# oa_sevenfortyfun.net
KiCad netlist of a schematic drawn in EAGLE
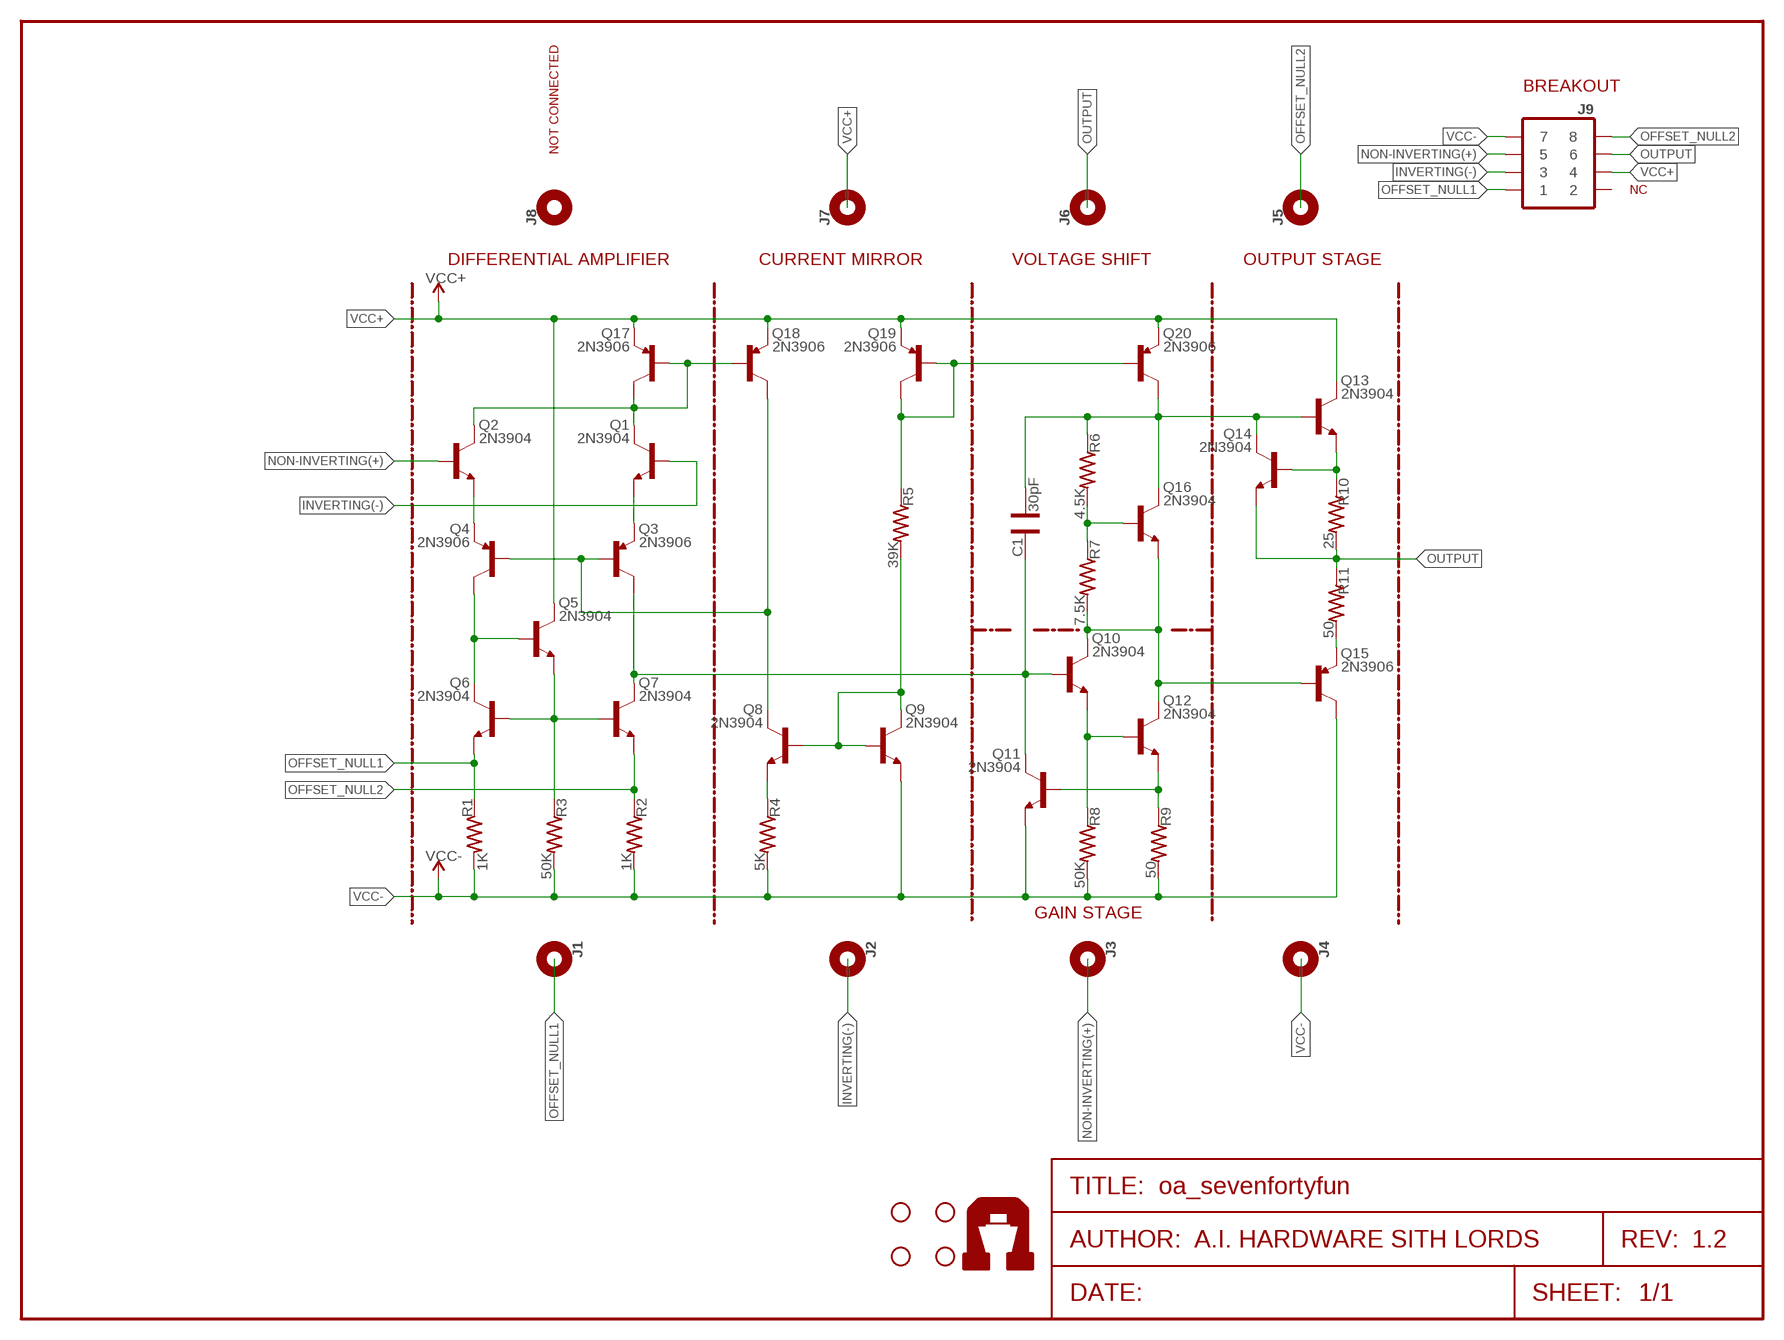
[diagram p0: schematic, sheet 1]

(export (version "E")
  (design (tool "Eeschema 10.0.6"))
  (components
    (comp (ref "C1")
      (value "30pF")
      (footprint "eagle-import:CAP-025X050")
      (libsource (lib "eagle-import") (part "CAP025X050"))
    )
    (comp (ref "J1")
      (value "1X01-TERM")
      (footprint "eagle-import:1X01-TERM")
      (libsource (lib "eagle-import") (part "1X01-TERM"))
    )
    (comp (ref "J2")
      (value "1X01-TERM")
      (footprint "eagle-import:1X01-TERM")
      (libsource (lib "eagle-import") (part "1X01-TERM"))
    )
    (comp (ref "J3")
      (value "1X01-TERM")
      (footprint "eagle-import:1X01-TERM")
      (libsource (lib "eagle-import") (part "1X01-TERM"))
    )
    (comp (ref "J4")
      (value "1X01-TERM")
      (footprint "eagle-import:1X01-TERM")
      (libsource (lib "eagle-import") (part "1X01-TERM"))
    )
    (comp (ref "J5")
      (value "1X01-TERM")
      (footprint "eagle-import:1X01-TERM")
      (libsource (lib "eagle-import") (part "1X01-TERM"))
    )
    (comp (ref "J6")
      (value "1X01-TERM")
      (footprint "eagle-import:1X01-TERM")
      (libsource (lib "eagle-import") (part "1X01-TERM"))
    )
    (comp (ref "J7")
      (value "1X01-TERM")
      (footprint "eagle-import:1X01-TERM")
      (libsource (lib "eagle-import") (part "1X01-TERM"))
    )
    (comp (ref "J8")
      (value "1X01-TERM")
      (footprint "eagle-import:1X01-TERM")
      (libsource (lib "eagle-import") (part "1X01-TERM"))
    )
    (comp (ref "J9")
      (value "2X04SHR")
      (footprint "eagle-import:2X04-SHR")
      (libsource (lib "eagle-import") (part "2X04SHR"))
    )
    (comp (ref "Q1")
      (value "2N3904")
      (footprint "eagle-import:TO-92-NPN")
      (libsource (lib "eagle-import") (part "BJT-NPN"))
    )
    (comp (ref "Q2")
      (value "2N3904")
      (footprint "eagle-import:TO-92-NPN")
      (libsource (lib "eagle-import") (part "BJT-NPN"))
    )
    (comp (ref "Q3")
      (value "2N3906")
      (footprint "eagle-import:TO-92-PNP")
      (libsource (lib "eagle-import") (part "BJT-PNP"))
    )
    (comp (ref "Q4")
      (value "2N3906")
      (footprint "eagle-import:TO-92-PNP")
      (libsource (lib "eagle-import") (part "BJT-PNP"))
    )
    (comp (ref "Q5")
      (value "2N3904")
      (footprint "eagle-import:TO-92-NPN")
      (libsource (lib "eagle-import") (part "BJT-NPN"))
    )
    (comp (ref "Q6")
      (value "2N3904")
      (footprint "eagle-import:TO-92-NPN")
      (libsource (lib "eagle-import") (part "BJT-NPN"))
    )
    (comp (ref "Q7")
      (value "2N3904")
      (footprint "eagle-import:TO-92-NPN")
      (libsource (lib "eagle-import") (part "BJT-NPN"))
    )
    (comp (ref "Q8")
      (value "2N3904")
      (footprint "eagle-import:TO-92-NPN")
      (libsource (lib "eagle-import") (part "BJT-NPN"))
    )
    (comp (ref "Q9")
      (value "2N3904")
      (footprint "eagle-import:TO-92-NPN")
      (libsource (lib "eagle-import") (part "BJT-NPN"))
    )
    (comp (ref "Q10")
      (value "2N3904")
      (footprint "eagle-import:TO-92-NPN")
      (libsource (lib "eagle-import") (part "BJT-NPN"))
    )
    (comp (ref "Q11")
      (value "2N3904")
      (footprint "eagle-import:TO-92-NPN")
      (libsource (lib "eagle-import") (part "BJT-NPN"))
    )
    (comp (ref "Q12")
      (value "2N3904")
      (footprint "eagle-import:TO-92-NPN")
      (libsource (lib "eagle-import") (part "BJT-NPN"))
    )
    (comp (ref "Q13")
      (value "2N3904")
      (footprint "eagle-import:TO-92-NPN")
      (libsource (lib "eagle-import") (part "BJT-NPN"))
    )
    (comp (ref "Q14")
      (value "2N3904")
      (footprint "eagle-import:TO-92-NPN")
      (libsource (lib "eagle-import") (part "BJT-NPN"))
    )
    (comp (ref "Q15")
      (value "2N3906")
      (footprint "eagle-import:TO-92-PNP")
      (libsource (lib "eagle-import") (part "BJT-PNP"))
    )
    (comp (ref "Q16")
      (value "2N3904")
      (footprint "eagle-import:TO-92-NPN")
      (libsource (lib "eagle-import") (part "BJT-NPN"))
    )
    (comp (ref "Q17")
      (value "2N3906")
      (footprint "eagle-import:TO-92-PNP")
      (libsource (lib "eagle-import") (part "BJT-PNP"))
    )
    (comp (ref "Q18")
      (value "2N3906")
      (footprint "eagle-import:TO-92-PNP")
      (libsource (lib "eagle-import") (part "BJT-PNP"))
    )
    (comp (ref "Q19")
      (value "2N3906")
      (footprint "eagle-import:TO-92-PNP")
      (libsource (lib "eagle-import") (part "BJT-PNP"))
    )
    (comp (ref "Q20")
      (value "2N3906")
      (footprint "eagle-import:TO-92-PNP")
      (libsource (lib "eagle-import") (part "BJT-PNP"))
    )
    (comp (ref "R1")
      (value "1K")
      (footprint "eagle-import:RES-AXIAL-0.4")
      (libsource (lib "eagle-import") (part "RESAXIAL-0.4"))
    )
    (comp (ref "R2")
      (value "1K")
      (footprint "eagle-import:RES-AXIAL-0.4")
      (libsource (lib "eagle-import") (part "RESAXIAL-0.4"))
    )
    (comp (ref "R3")
      (value "50K")
      (footprint "eagle-import:RES-AXIAL-0.4")
      (libsource (lib "eagle-import") (part "RESAXIAL-0.4"))
    )
    (comp (ref "R4")
      (value "5K")
      (footprint "eagle-import:RES-AXIAL-0.4")
      (libsource (lib "eagle-import") (part "RESAXIAL-0.4"))
    )
    (comp (ref "R5")
      (value "39K")
      (footprint "eagle-import:RES-AXIAL-0.4")
      (libsource (lib "eagle-import") (part "RESAXIAL-0.4"))
    )
    (comp (ref "R6")
      (value "4.5K")
      (footprint "eagle-import:RES-AXIAL-0.4")
      (libsource (lib "eagle-import") (part "RESAXIAL-0.4"))
    )
    (comp (ref "R7")
      (value "7.5K")
      (footprint "eagle-import:RES-AXIAL-0.4")
      (libsource (lib "eagle-import") (part "RESAXIAL-0.4"))
    )
    (comp (ref "R8")
      (value "50K")
      (footprint "eagle-import:RES-AXIAL-0.4")
      (libsource (lib "eagle-import") (part "RESAXIAL-0.4"))
    )
    (comp (ref "R9")
      (value "50")
      (footprint "eagle-import:RES-AXIAL-0.4")
      (libsource (lib "eagle-import") (part "RESAXIAL-0.4"))
    )
    (comp (ref "R10")
      (value "25")
      (footprint "eagle-import:RES-AXIAL-0.4")
      (libsource (lib "eagle-import") (part "RESAXIAL-0.4"))
    )
    (comp (ref "R11")
      (value "50")
      (footprint "eagle-import:RES-AXIAL-0.4")
      (libsource (lib "eagle-import") (part "RESAXIAL-0.4"))
    )
    (comp (ref "STANDOFF1")
      (value "STAND-OFF4")
      (footprint "eagle-import:STAND-OFF-4")
      (libsource (lib "eagle-import") (part "STAND-OFF4"))
    )
    (comp (ref "STANDOFF2")
      (value "STAND-OFF4")
      (footprint "eagle-import:STAND-OFF-4")
      (libsource (lib "eagle-import") (part "STAND-OFF4"))
    )
    (comp (ref "STANDOFF3")
      (value "STAND-OFF4")
      (footprint "eagle-import:STAND-OFF-4")
      (libsource (lib "eagle-import") (part "STAND-OFF4"))
    )
    (comp (ref "STANDOFF4")
      (value "STAND-OFF4")
      (footprint "eagle-import:STAND-OFF-4")
      (libsource (lib "eagle-import") (part "STAND-OFF4"))
    )
    (comp (ref "U$3")
      (value "AI-LOGOL")
      (footprint "eagle-import:AI-LOGO-L")
      (libsource (lib "eagle-import") (part "AI-LOGOL"))
    )
  )
  (nets
    (net (code "1") (name "INVERTING(-)") (class "Default")
      (node (ref "J2") (pin "1") (pinfunction "1_1") (pintype "bidirectional"))
      (node (ref "J9") (pin "3") (pinfunction "3_3") (pintype "bidirectional"))
      (node (ref "Q1") (pin "2") (pinfunction "B_2") (pintype "passive"))
    )
    (net (code "2") (name "NON-INVERTING(+)") (class "Default")
      (node (ref "J3") (pin "1") (pinfunction "1_1") (pintype "bidirectional"))
      (node (ref "J9") (pin "5") (pinfunction "5_5") (pintype "bidirectional"))
      (node (ref "Q2") (pin "2") (pinfunction "B_2") (pintype "passive"))
    )
    (net (code "3") (name "Net-(Q1-C)") (class "Default")
      (node (ref "Q1") (pin "3") (pinfunction "C_3") (pintype "passive"))
      (node (ref "Q17") (pin "1") (pinfunction "C_1") (pintype "passive"))
      (node (ref "Q17") (pin "2") (pinfunction "B_2") (pintype "passive"))
      (node (ref "Q18") (pin "2") (pinfunction "B_2") (pintype "passive"))
      (node (ref "Q2") (pin "3") (pinfunction "C_3") (pintype "passive"))
    )
    (net (code "4") (name "Net-(Q1-E)") (class "Default")
      (node (ref "Q1") (pin "1") (pinfunction "E_1") (pintype "passive"))
      (node (ref "Q3") (pin "3") (pinfunction "E_3") (pintype "passive"))
    )
    (net (code "5") (name "Net-(Q2-E)") (class "Default")
      (node (ref "Q2") (pin "1") (pinfunction "E_1") (pintype "passive"))
      (node (ref "Q4") (pin "3") (pinfunction "E_3") (pintype "passive"))
    )
    (net (code "6") (name "Net-(Q4-C)") (class "Default")
      (node (ref "Q4") (pin "1") (pinfunction "C_1") (pintype "passive"))
      (node (ref "Q5") (pin "2") (pinfunction "B_2") (pintype "passive"))
      (node (ref "Q6") (pin "3") (pinfunction "C_3") (pintype "passive"))
    )
    (net (code "7") (name "Net-(Q5-E)") (class "Default")
      (node (ref "Q5") (pin "1") (pinfunction "E_1") (pintype "passive"))
      (node (ref "Q6") (pin "2") (pinfunction "B_2") (pintype "passive"))
      (node (ref "Q7") (pin "2") (pinfunction "B_2") (pintype "passive"))
      (node (ref "R3") (pin "P$1") (pinfunction "1_P$1") (pintype "passive"))
    )
    (net (code "8") (name "Net-(Q8-B)") (class "Default")
      (node (ref "Q8") (pin "2") (pinfunction "B_2") (pintype "passive"))
      (node (ref "Q9") (pin "2") (pinfunction "B_2") (pintype "passive"))
      (node (ref "Q9") (pin "3") (pinfunction "C_3") (pintype "passive"))
      (node (ref "R5") (pin "P$2") (pinfunction "2_P$2") (pintype "passive"))
    )
    (net (code "9") (name "Net-(Q8-E)") (class "Default")
      (node (ref "Q8") (pin "1") (pinfunction "E_1") (pintype "passive"))
      (node (ref "R4") (pin "P$1") (pinfunction "1_P$1") (pintype "passive"))
    )
    (net (code "10") (name "Net-(Q10-B)") (class "Default")
      (node (ref "C1") (pin "2") (pinfunction "2_2") (pintype "passive"))
      (node (ref "Q10") (pin "2") (pinfunction "B_2") (pintype "passive"))
      (node (ref "Q11") (pin "3") (pinfunction "C_3") (pintype "passive"))
      (node (ref "Q3") (pin "1") (pinfunction "C_1") (pintype "passive"))
      (node (ref "Q7") (pin "3") (pinfunction "C_3") (pintype "passive"))
    )
    (net (code "11") (name "Net-(Q10-C)") (class "Default")
      (node (ref "Q10") (pin "3") (pinfunction "C_3") (pintype "passive"))
      (node (ref "Q12") (pin "3") (pinfunction "C_3") (pintype "passive"))
      (node (ref "Q15") (pin "2") (pinfunction "B_2") (pintype "passive"))
      (node (ref "Q16") (pin "1") (pinfunction "E_1") (pintype "passive"))
      (node (ref "R7") (pin "P$2") (pinfunction "2_P$2") (pintype "passive"))
    )
    (net (code "12") (name "Net-(Q10-E)") (class "Default")
      (node (ref "Q10") (pin "1") (pinfunction "E_1") (pintype "passive"))
      (node (ref "Q12") (pin "2") (pinfunction "B_2") (pintype "passive"))
      (node (ref "R8") (pin "P$1") (pinfunction "1_P$1") (pintype "passive"))
    )
    (net (code "13") (name "Net-(Q11-B)") (class "Default")
      (node (ref "Q11") (pin "2") (pinfunction "B_2") (pintype "passive"))
      (node (ref "Q12") (pin "1") (pinfunction "E_1") (pintype "passive"))
      (node (ref "R9") (pin "P$1") (pinfunction "1_P$1") (pintype "passive"))
    )
    (net (code "14") (name "Net-(Q13-B)") (class "Default")
      (node (ref "C1") (pin "1") (pinfunction "1_1") (pintype "passive"))
      (node (ref "Q13") (pin "2") (pinfunction "B_2") (pintype "passive"))
      (node (ref "Q14") (pin "3") (pinfunction "C_3") (pintype "passive"))
      (node (ref "Q16") (pin "3") (pinfunction "C_3") (pintype "passive"))
      (node (ref "Q20") (pin "1") (pinfunction "C_1") (pintype "passive"))
      (node (ref "R6") (pin "P$1") (pinfunction "1_P$1") (pintype "passive"))
    )
    (net (code "15") (name "Net-(Q13-E)") (class "Default")
      (node (ref "Q13") (pin "1") (pinfunction "E_1") (pintype "passive"))
      (node (ref "Q14") (pin "2") (pinfunction "B_2") (pintype "passive"))
      (node (ref "R10") (pin "P$1") (pinfunction "1_P$1") (pintype "passive"))
    )
    (net (code "16") (name "Net-(Q15-E)") (class "Default")
      (node (ref "Q15") (pin "3") (pinfunction "E_3") (pintype "passive"))
      (node (ref "R11") (pin "P$2") (pinfunction "2_P$2") (pintype "passive"))
    )
    (net (code "17") (name "Net-(Q16-B)") (class "Default")
      (node (ref "Q16") (pin "2") (pinfunction "B_2") (pintype "passive"))
      (node (ref "R6") (pin "P$2") (pinfunction "2_P$2") (pintype "passive"))
      (node (ref "R7") (pin "P$1") (pinfunction "1_P$1") (pintype "passive"))
    )
    (net (code "18") (name "Net-(Q18-C)") (class "Default")
      (node (ref "Q18") (pin "1") (pinfunction "C_1") (pintype "passive"))
      (node (ref "Q3") (pin "2") (pinfunction "B_2") (pintype "passive"))
      (node (ref "Q4") (pin "2") (pinfunction "B_2") (pintype "passive"))
      (node (ref "Q8") (pin "3") (pinfunction "C_3") (pintype "passive"))
    )
    (net (code "19") (name "Net-(Q19-B)") (class "Default")
      (node (ref "Q19") (pin "1") (pinfunction "C_1") (pintype "passive"))
      (node (ref "Q19") (pin "2") (pinfunction "B_2") (pintype "passive"))
      (node (ref "Q20") (pin "2") (pinfunction "B_2") (pintype "passive"))
      (node (ref "R5") (pin "P$1") (pinfunction "1_P$1") (pintype "passive"))
    )
    (net (code "20") (name "OFFSET_NULL1") (class "Default")
      (node (ref "J1") (pin "1") (pinfunction "1_1") (pintype "bidirectional"))
      (node (ref "J9") (pin "1") (pinfunction "1_1") (pintype "bidirectional"))
      (node (ref "Q6") (pin "1") (pinfunction "E_1") (pintype "passive"))
      (node (ref "R1") (pin "P$1") (pinfunction "1_P$1") (pintype "passive"))
    )
    (net (code "21") (name "OFFSET_NULL2") (class "Default")
      (node (ref "J5") (pin "1") (pinfunction "1_1") (pintype "bidirectional"))
      (node (ref "J9") (pin "8") (pinfunction "8_8") (pintype "bidirectional"))
      (node (ref "Q7") (pin "1") (pinfunction "E_1") (pintype "passive"))
      (node (ref "R2") (pin "P$1") (pinfunction "1_P$1") (pintype "passive"))
    )
    (net (code "22") (name "OUTPUT") (class "Default")
      (node (ref "J6") (pin "1") (pinfunction "1_1") (pintype "bidirectional"))
      (node (ref "J9") (pin "6") (pinfunction "6_6") (pintype "bidirectional"))
      (node (ref "Q14") (pin "1") (pinfunction "E_1") (pintype "passive"))
      (node (ref "R10") (pin "P$2") (pinfunction "2_P$2") (pintype "passive"))
      (node (ref "R11") (pin "P$1") (pinfunction "1_P$1") (pintype "passive"))
    )
    (net (code "23") (name "VCC+") (class "Default")
      (node (ref "J7") (pin "1") (pinfunction "1_1") (pintype "bidirectional"))
      (node (ref "J9") (pin "4") (pinfunction "4_4") (pintype "bidirectional"))
      (node (ref "Q13") (pin "3") (pinfunction "C_3") (pintype "passive"))
      (node (ref "Q17") (pin "3") (pinfunction "E_3") (pintype "passive"))
      (node (ref "Q18") (pin "3") (pinfunction "E_3") (pintype "passive"))
      (node (ref "Q19") (pin "3") (pinfunction "E_3") (pintype "passive"))
      (node (ref "Q20") (pin "3") (pinfunction "E_3") (pintype "passive"))
      (node (ref "Q5") (pin "3") (pinfunction "C_3") (pintype "passive"))
    )
    (net (code "24") (name "VCC-") (class "Default")
      (node (ref "J4") (pin "1") (pinfunction "1_1") (pintype "bidirectional"))
      (node (ref "J9") (pin "7") (pinfunction "7_7") (pintype "bidirectional"))
      (node (ref "Q11") (pin "1") (pinfunction "E_1") (pintype "passive"))
      (node (ref "Q15") (pin "1") (pinfunction "C_1") (pintype "passive"))
      (node (ref "Q9") (pin "1") (pinfunction "E_1") (pintype "passive"))
      (node (ref "R1") (pin "P$2") (pinfunction "2_P$2") (pintype "passive"))
      (node (ref "R2") (pin "P$2") (pinfunction "2_P$2") (pintype "passive"))
      (node (ref "R3") (pin "P$2") (pinfunction "2_P$2") (pintype "passive"))
      (node (ref "R4") (pin "P$2") (pinfunction "2_P$2") (pintype "passive"))
      (node (ref "R8") (pin "P$2") (pinfunction "2_P$2") (pintype "passive"))
      (node (ref "R9") (pin "P$2") (pinfunction "2_P$2") (pintype "passive"))
    )
    (net (code "25") (name "unconnected-(J8-Pad1)") (class "Default")
      (node (ref "J8") (pin "1") (pinfunction "1_1") (pintype "bidirectional"))
    )
    (net (code "26") (name "unconnected-(J9-Pad2)") (class "Default")
      (node (ref "J9") (pin "2") (pinfunction "2_2") (pintype "bidirectional"))
    )
  )
)
